# scheme1.net
KiCad netlist of a schematic drawn in EAGLE
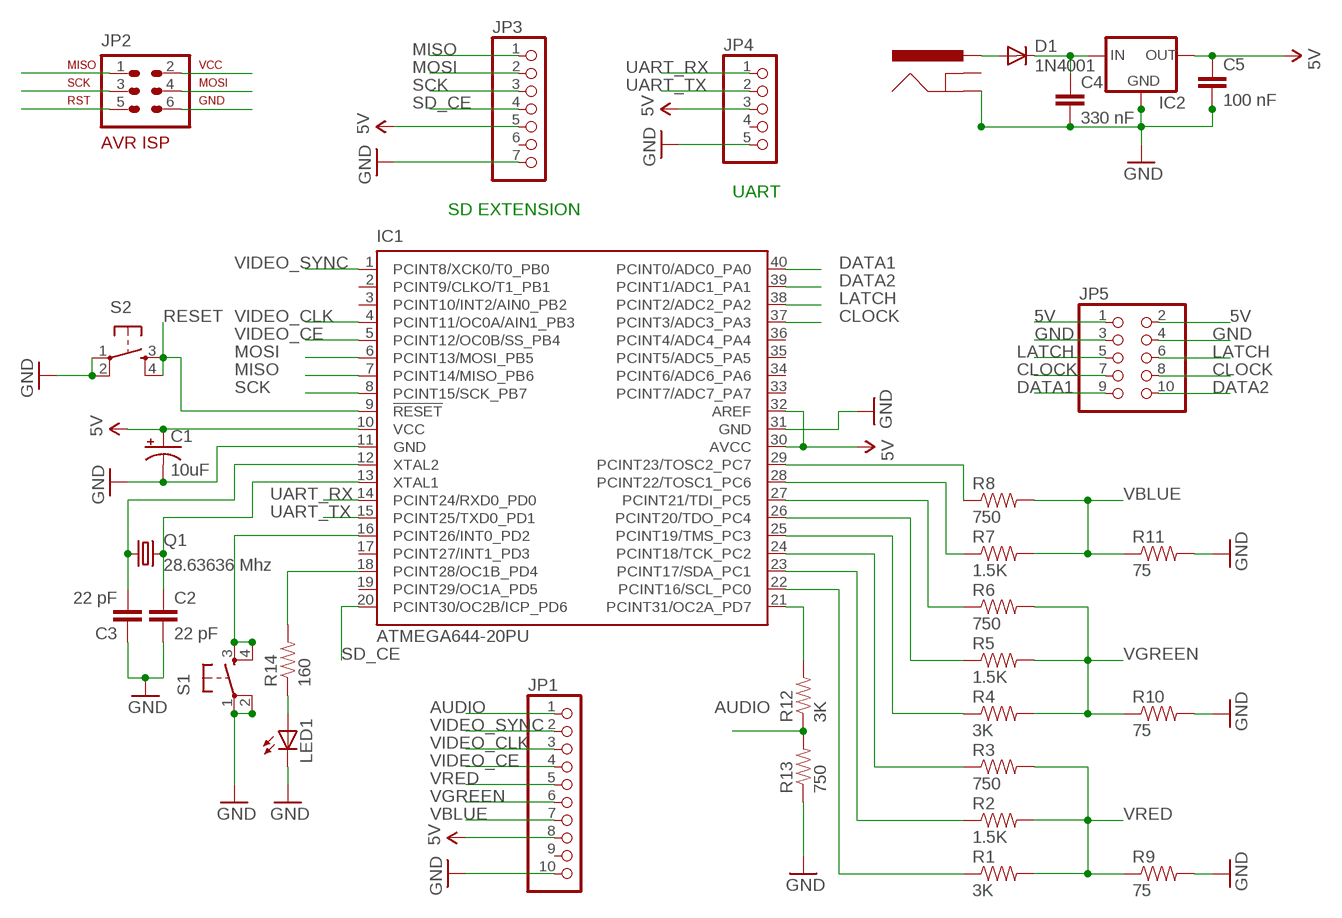
[diagram p0: schematic, sheet 1]

(export (version "E")
  (design (tool "Eeschema 10.0.6"))
  (components
    (comp (ref "C1")
      (value "10uF")
      (footprint "eagle-import:CPOL-RADIAL-10UF-25V")
      (libsource (lib "eagle-import") (part "CAP_POLPTH2"))
    )
    (comp (ref "C2")
      (value "22 pF")
      (footprint "eagle-import:CAP-PTH-SMALL")
      (libsource (lib "eagle-import") (part "CAPPTH"))
    )
    (comp (ref "C3")
      (value "22 pF")
      (footprint "eagle-import:CAP-PTH-SMALL")
      (libsource (lib "eagle-import") (part "CAPPTH"))
    )
    (comp (ref "C4")
      (value "330 nF")
      (footprint "eagle-import:CAP-PTH-SMALL")
      (libsource (lib "eagle-import") (part "CAPPTH"))
    )
    (comp (ref "C5")
      (value "100 nF")
      (footprint "eagle-import:CAP-PTH-SMALL")
      (libsource (lib "eagle-import") (part "CAPPTH"))
    )
    (comp (ref "D1")
      (value "1N4001")
      (footprint "eagle-import:DIODE-1N4001")
      (libsource (lib "eagle-import") (part "DIODEPTH"))
    )
    (comp (ref "IC1")
      (value "ATMEGA644-20PU")
      (footprint "eagle-import:DIL40")
      (libsource (lib "eagle-import") (part "ATMEGA644-PU20"))
    )
    (comp (ref "IC2")
      (value "V_REG_78XXSIDE")
      (footprint "eagle-import:78XXL")
      (libsource (lib "eagle-import") (part "V_REG_78XXSIDE"))
    )
    (comp (ref "J1")
      (value "POWER_JACKSLT")
      (footprint "eagle-import:POWER_JACK_SLOT")
      (libsource (lib "eagle-import") (part "POWER_JACKSLT"))
    )
    (comp (ref "JP1")
      (value "PINHD-1X10")
      (footprint "eagle-import:1X10")
      (libsource (lib "eagle-import") (part "PINHD-1X10"))
    )
    (comp (ref "JP2")
      (value "AVR-ISP-6VERT")
      (footprint "eagle-import:AVR-ISP-6")
      (libsource (lib "eagle-import") (part "AVR-ISP-6VERT"))
    )
    (comp (ref "JP3")
      (value "PINHD-1X7")
      (footprint "eagle-import:1X07")
      (libsource (lib "eagle-import") (part "PINHD-1X7"))
    )
    (comp (ref "JP4")
      (value "PINHD-1X5")
      (footprint "eagle-import:1X05")
      (libsource (lib "eagle-import") (part "PINHD-1X5"))
    )
    (comp (ref "JP5")
      (value "PINHD-2X5")
      (footprint "eagle-import:2X05")
      (libsource (lib "eagle-import") (part "PINHD-2X5"))
    )
    (comp (ref "LED1")
      (value "LED3MM")
      (footprint "eagle-import:LED3MM")
      (libsource (lib "eagle-import") (part "LED3MM"))
    )
    (comp (ref "Q1")
      (value "28.63636 Mhz")
      (footprint "eagle-import:HC49US")
      (libsource (lib "eagle-import") (part "CRYSTALHC49US"))
    )
    (comp (ref "R1")
      (value "3K")
      (footprint "eagle-import:AXIAL-0.3")
      (libsource (lib "eagle-import") (part "RESISTORPTH1"))
    )
    (comp (ref "R2")
      (value "1.5K")
      (footprint "eagle-import:AXIAL-0.3")
      (libsource (lib "eagle-import") (part "RESISTORPTH1"))
    )
    (comp (ref "R3")
      (value "750")
      (footprint "eagle-import:AXIAL-0.3")
      (libsource (lib "eagle-import") (part "RESISTORPTH1"))
    )
    (comp (ref "R4")
      (value "3K")
      (footprint "eagle-import:AXIAL-0.3")
      (libsource (lib "eagle-import") (part "RESISTORPTH1"))
    )
    (comp (ref "R5")
      (value "1.5K")
      (footprint "eagle-import:AXIAL-0.3")
      (libsource (lib "eagle-import") (part "RESISTORPTH1"))
    )
    (comp (ref "R6")
      (value "750")
      (footprint "eagle-import:AXIAL-0.3")
      (libsource (lib "eagle-import") (part "RESISTORPTH1"))
    )
    (comp (ref "R7")
      (value "1.5K")
      (footprint "eagle-import:AXIAL-0.3")
      (libsource (lib "eagle-import") (part "RESISTORPTH1"))
    )
    (comp (ref "R8")
      (value "750")
      (footprint "eagle-import:AXIAL-0.3")
      (libsource (lib "eagle-import") (part "RESISTORPTH1"))
    )
    (comp (ref "R9")
      (value "75")
      (footprint "eagle-import:AXIAL-0.3")
      (libsource (lib "eagle-import") (part "RESISTORPTH1"))
    )
    (comp (ref "R10")
      (value "75")
      (footprint "eagle-import:AXIAL-0.3")
      (libsource (lib "eagle-import") (part "RESISTORPTH1"))
    )
    (comp (ref "R11")
      (value "75")
      (footprint "eagle-import:AXIAL-0.3")
      (libsource (lib "eagle-import") (part "RESISTORPTH1"))
    )
    (comp (ref "R12")
      (value "3K")
      (footprint "eagle-import:AXIAL-0.3")
      (libsource (lib "eagle-import") (part "RESISTORPTH1"))
    )
    (comp (ref "R13")
      (value "750")
      (footprint "eagle-import:AXIAL-0.3")
      (libsource (lib "eagle-import") (part "RESISTORPTH1"))
    )
    (comp (ref "R14")
      (value "160")
      (footprint "eagle-import:AXIAL-0.3")
      (libsource (lib "eagle-import") (part "RESISTORPTH1"))
    )
    (comp (ref "S1")
      (value "TAC_SWITCHPTH")
      (footprint "eagle-import:TACTILE-PTH")
      (libsource (lib "eagle-import") (part "TAC_SWITCHPTH"))
    )
    (comp (ref "S2")
      (value "TAC_SWITCHPTH")
      (footprint "eagle-import:TACTILE-PTH")
      (libsource (lib "eagle-import") (part "TAC_SWITCHPTH"))
    )
  )
  (nets
    (net (code "1") (name "/AUDIO") (class "Default")
      (node (ref "JP1") (pin "1") (pinfunction "1_1") (pintype "passive"))
      (node (ref "R12") (pin "P$1") (pinfunction "1_P$1") (pintype "passive"))
      (node (ref "R13") (pin "P$2") (pinfunction "2_P$2") (pintype "passive"))
    )
    (net (code "2") (name "/CLOCK") (class "Default")
      (node (ref "IC1") (pin "37") (pinfunction "PCINT3/ADC3_PA3_37") (pintype "bidirectional"))
      (node (ref "JP5") (pin "7") (pinfunction "7_7") (pintype "passive"))
      (node (ref "JP5") (pin "8") (pinfunction "8_8") (pintype "passive"))
    )
    (net (code "3") (name "/DATA1") (class "Default")
      (node (ref "IC1") (pin "40") (pinfunction "PCINT0/ADC0_PA0_40") (pintype "bidirectional"))
      (node (ref "JP5") (pin "9") (pinfunction "9_9") (pintype "passive"))
    )
    (net (code "4") (name "/DATA2") (class "Default")
      (node (ref "IC1") (pin "39") (pinfunction "PCINT1/ADC1_PA1_39") (pintype "bidirectional"))
      (node (ref "JP5") (pin "10") (pinfunction "10_10") (pintype "passive"))
    )
    (net (code "5") (name "/LATCH") (class "Default")
      (node (ref "IC1") (pin "38") (pinfunction "PCINT2/ADC2_PA2_38") (pintype "bidirectional"))
      (node (ref "JP5") (pin "5") (pinfunction "5_5") (pintype "passive"))
      (node (ref "JP5") (pin "6") (pinfunction "6_6") (pintype "passive"))
    )
    (net (code "6") (name "/MISO") (class "Default")
      (node (ref "IC1") (pin "7") (pinfunction "PCINT14/MISO_PB6_7") (pintype "bidirectional"))
      (node (ref "JP2") (pin "1") (pinfunction "1_1") (pintype "passive"))
      (node (ref "JP3") (pin "1") (pinfunction "1_1") (pintype "passive"))
    )
    (net (code "7") (name "/MOSI") (class "Default")
      (node (ref "IC1") (pin "6") (pinfunction "PCINT13/MOSI_PB5_6") (pintype "bidirectional"))
      (node (ref "JP2") (pin "4") (pinfunction "4_4") (pintype "passive"))
      (node (ref "JP3") (pin "2") (pinfunction "2_2") (pintype "passive"))
    )
    (net (code "8") (name "/RESET") (class "Default")
      (node (ref "IC1") (pin "9") (pinfunction "~{RESET}_9") (pintype "input"))
      (node (ref "JP2") (pin "5") (pinfunction "5_5") (pintype "passive"))
      (node (ref "S2") (pin "3") (pinfunction "3_3") (pintype "passive"))
      (node (ref "S2") (pin "4") (pinfunction "4_4") (pintype "passive"))
    )
    (net (code "9") (name "/SCK") (class "Default")
      (node (ref "IC1") (pin "8") (pinfunction "PCINT15/SCK_PB7_8") (pintype "bidirectional"))
      (node (ref "JP2") (pin "3") (pinfunction "3_3") (pintype "passive"))
      (node (ref "JP3") (pin "3") (pinfunction "3_3") (pintype "passive"))
    )
    (net (code "10") (name "/SD_CE") (class "Default")
      (node (ref "IC1") (pin "20") (pinfunction "PCINT30/OC2B/ICP_PD6_20") (pintype "bidirectional"))
      (node (ref "JP3") (pin "4") (pinfunction "4_4") (pintype "passive"))
    )
    (net (code "11") (name "/UART_RX") (class "Default")
      (node (ref "IC1") (pin "14") (pinfunction "PCINT24/RXD0_PD0_14") (pintype "bidirectional"))
      (node (ref "JP4") (pin "1") (pinfunction "1_1") (pintype "passive"))
    )
    (net (code "12") (name "/UART_TX") (class "Default")
      (node (ref "IC1") (pin "15") (pinfunction "PCINT25/TXD0_PD1_15") (pintype "bidirectional"))
      (node (ref "JP4") (pin "2") (pinfunction "2_2") (pintype "passive"))
    )
    (net (code "13") (name "/VBLUE") (class "Default")
      (node (ref "JP1") (pin "7") (pinfunction "7_7") (pintype "passive"))
      (node (ref "R11") (pin "P$1") (pinfunction "1_P$1") (pintype "passive"))
      (node (ref "R7") (pin "P$2") (pinfunction "2_P$2") (pintype "passive"))
      (node (ref "R8") (pin "P$2") (pinfunction "2_P$2") (pintype "passive"))
    )
    (net (code "14") (name "/VGREEN") (class "Default")
      (node (ref "JP1") (pin "6") (pinfunction "6_6") (pintype "passive"))
      (node (ref "R10") (pin "P$1") (pinfunction "1_P$1") (pintype "passive"))
      (node (ref "R4") (pin "P$2") (pinfunction "2_P$2") (pintype "passive"))
      (node (ref "R5") (pin "P$2") (pinfunction "2_P$2") (pintype "passive"))
      (node (ref "R6") (pin "P$2") (pinfunction "2_P$2") (pintype "passive"))
    )
    (net (code "15") (name "/VIDEO_CE") (class "Default")
      (node (ref "IC1") (pin "5") (pinfunction "PCINT12/OC0B/SS_PB4_5") (pintype "bidirectional"))
      (node (ref "JP1") (pin "4") (pinfunction "4_4") (pintype "passive"))
    )
    (net (code "16") (name "/VIDEO_CLK") (class "Default")
      (node (ref "IC1") (pin "4") (pinfunction "PCINT11/OC0A/AIN1_PB3_4") (pintype "bidirectional"))
      (node (ref "JP1") (pin "3") (pinfunction "3_3") (pintype "passive"))
    )
    (net (code "17") (name "/VIDEO_SYNC") (class "Default")
      (node (ref "IC1") (pin "1") (pinfunction "PCINT8/XCK0/T0_PB0_1") (pintype "bidirectional"))
      (node (ref "JP1") (pin "2") (pinfunction "2_2") (pintype "passive"))
    )
    (net (code "18") (name "/VRED") (class "Default")
      (node (ref "JP1") (pin "5") (pinfunction "5_5") (pintype "passive"))
      (node (ref "R1") (pin "P$2") (pinfunction "2_P$2") (pintype "passive"))
      (node (ref "R2") (pin "P$2") (pinfunction "2_P$2") (pintype "passive"))
      (node (ref "R3") (pin "P$2") (pinfunction "2_P$2") (pintype "passive"))
      (node (ref "R9") (pin "P$1") (pinfunction "1_P$1") (pintype "passive"))
    )
    (net (code "19") (name "5V") (class "Default")
      (node (ref "C1") (pin "1") (pinfunction "+_1") (pintype "passive"))
      (node (ref "C5") (pin "1") (pinfunction "1_1") (pintype "passive"))
      (node (ref "IC1") (pin "10") (pinfunction "VCC_10") (pintype "power_in"))
      (node (ref "IC1") (pin "30") (pinfunction "AVCC_30") (pintype "power_in"))
      (node (ref "IC1") (pin "32") (pinfunction "AREF_32") (pintype "passive"))
      (node (ref "IC2") (pin "OUT") (pinfunction "OUT_OUT") (pintype "output"))
      (node (ref "JP1") (pin "8") (pinfunction "8_8") (pintype "passive"))
      (node (ref "JP2") (pin "2") (pinfunction "2_2") (pintype "passive"))
      (node (ref "JP3") (pin "5") (pinfunction "5_5") (pintype "passive"))
      (node (ref "JP4") (pin "3") (pinfunction "3_3") (pintype "passive"))
      (node (ref "JP5") (pin "1") (pinfunction "1_1") (pintype "passive"))
      (node (ref "JP5") (pin "2") (pinfunction "2_2") (pintype "passive"))
    )
    (net (code "20") (name "GND") (class "Default")
      (node (ref "C1") (pin "2") (pinfunction "-_2") (pintype "passive"))
      (node (ref "C2") (pin "2") (pinfunction "2_2") (pintype "passive"))
      (node (ref "C3") (pin "1") (pinfunction "1_1") (pintype "passive"))
      (node (ref "C4") (pin "2") (pinfunction "2_2") (pintype "passive"))
      (node (ref "C5") (pin "2") (pinfunction "2_2") (pintype "passive"))
      (node (ref "IC1") (pin "11") (pinfunction "GND_11") (pintype "power_in"))
      (node (ref "IC1") (pin "31") (pinfunction "GND_31") (pintype "power_in"))
      (node (ref "IC2") (pin "GND") (pinfunction "GND_GND") (pintype "input"))
      (node (ref "J1") (pin "GND@2") (pinfunction "GND_GND@2") (pintype "bidirectional"))
      (node (ref "JP1") (pin "10") (pinfunction "10_10") (pintype "passive"))
      (node (ref "JP2") (pin "6") (pinfunction "6_6") (pintype "passive"))
      (node (ref "JP3") (pin "7") (pinfunction "7_7") (pintype "passive"))
      (node (ref "JP4") (pin "5") (pinfunction "5_5") (pintype "passive"))
      (node (ref "JP5") (pin "3") (pinfunction "3_3") (pintype "passive"))
      (node (ref "JP5") (pin "4") (pinfunction "4_4") (pintype "passive"))
      (node (ref "LED1") (pin "K") (pinfunction "C_K") (pintype "passive"))
      (node (ref "R10") (pin "P$2") (pinfunction "2_P$2") (pintype "passive"))
      (node (ref "R11") (pin "P$2") (pinfunction "2_P$2") (pintype "passive"))
      (node (ref "R13") (pin "P$1") (pinfunction "1_P$1") (pintype "passive"))
      (node (ref "R9") (pin "P$2") (pinfunction "2_P$2") (pintype "passive"))
      (node (ref "S1") (pin "1") (pinfunction "1_1") (pintype "passive"))
      (node (ref "S1") (pin "2") (pinfunction "2_2") (pintype "passive"))
      (node (ref "S2") (pin "1") (pinfunction "1_1") (pintype "passive"))
      (node (ref "S2") (pin "2") (pinfunction "2_2") (pintype "passive"))
    )
    (net (code "21") (name "Net-(C4-Pad1)") (class "Default")
      (node (ref "C4") (pin "1") (pinfunction "1_1") (pintype "passive"))
      (node (ref "D1") (pin "C") (pinfunction "C_C") (pintype "passive"))
      (node (ref "IC2") (pin "IN") (pinfunction "IN_IN") (pintype "input"))
    )
    (net (code "22") (name "Net-(D1-PadA)") (class "Default")
      (node (ref "D1") (pin "A") (pinfunction "A_A") (pintype "passive"))
      (node (ref "J1") (pin "PWR") (pinfunction "PWR_PWR") (pintype "bidirectional"))
    )
    (net (code "23") (name "Net-(IC1-PCINT16{slash}SCL_PC0)") (class "Default")
      (node (ref "IC1") (pin "22") (pinfunction "PCINT16/SCL_PC0_22") (pintype "bidirectional"))
      (node (ref "R1") (pin "P$1") (pinfunction "1_P$1") (pintype "passive"))
    )
    (net (code "24") (name "Net-(IC1-PCINT17{slash}SDA_PC1)") (class "Default")
      (node (ref "IC1") (pin "23") (pinfunction "PCINT17/SDA_PC1_23") (pintype "bidirectional"))
      (node (ref "R2") (pin "P$1") (pinfunction "1_P$1") (pintype "passive"))
    )
    (net (code "25") (name "Net-(IC1-PCINT18{slash}TCK_PC2)") (class "Default")
      (node (ref "IC1") (pin "24") (pinfunction "PCINT18/TCK_PC2_24") (pintype "bidirectional"))
      (node (ref "R3") (pin "P$1") (pinfunction "1_P$1") (pintype "passive"))
    )
    (net (code "26") (name "Net-(IC1-PCINT19{slash}TMS_PC3)") (class "Default")
      (node (ref "IC1") (pin "25") (pinfunction "PCINT19/TMS_PC3_25") (pintype "bidirectional"))
      (node (ref "R4") (pin "P$1") (pinfunction "1_P$1") (pintype "passive"))
    )
    (net (code "27") (name "Net-(IC1-PCINT20{slash}TDO_PC4)") (class "Default")
      (node (ref "IC1") (pin "26") (pinfunction "PCINT20/TDO_PC4_26") (pintype "bidirectional"))
      (node (ref "R5") (pin "P$1") (pinfunction "1_P$1") (pintype "passive"))
    )
    (net (code "28") (name "Net-(IC1-PCINT21{slash}TDI_PC5)") (class "Default")
      (node (ref "IC1") (pin "27") (pinfunction "PCINT21/TDI_PC5_27") (pintype "bidirectional"))
      (node (ref "R6") (pin "P$1") (pinfunction "1_P$1") (pintype "passive"))
    )
    (net (code "29") (name "Net-(IC1-PCINT22{slash}TOSC1_PC6)") (class "Default")
      (node (ref "IC1") (pin "28") (pinfunction "PCINT22/TOSC1_PC6_28") (pintype "bidirectional"))
      (node (ref "R7") (pin "P$1") (pinfunction "1_P$1") (pintype "passive"))
    )
    (net (code "30") (name "Net-(IC1-PCINT23{slash}TOSC2_PC7)") (class "Default")
      (node (ref "IC1") (pin "29") (pinfunction "PCINT23/TOSC2_PC7_29") (pintype "bidirectional"))
      (node (ref "R8") (pin "P$1") (pinfunction "1_P$1") (pintype "passive"))
    )
    (net (code "31") (name "Net-(IC1-PCINT26{slash}INT0_PD2)") (class "Default")
      (node (ref "IC1") (pin "16") (pinfunction "PCINT26/INT0_PD2_16") (pintype "bidirectional"))
      (node (ref "S1") (pin "3") (pinfunction "3_3") (pintype "passive"))
      (node (ref "S1") (pin "4") (pinfunction "4_4") (pintype "passive"))
    )
    (net (code "32") (name "Net-(IC1-PCINT28{slash}OC1B_PD4)") (class "Default")
      (node (ref "IC1") (pin "18") (pinfunction "PCINT28/OC1B_PD4_18") (pintype "bidirectional"))
      (node (ref "R14") (pin "P$2") (pinfunction "2_P$2") (pintype "passive"))
    )
    (net (code "33") (name "Net-(IC1-PCINT31{slash}OC2A_PD7)") (class "Default")
      (node (ref "IC1") (pin "21") (pinfunction "PCINT31/OC2A_PD7_21") (pintype "bidirectional"))
      (node (ref "R12") (pin "P$2") (pinfunction "2_P$2") (pintype "passive"))
    )
    (net (code "34") (name "Net-(IC1-XTAL1)") (class "Default")
      (node (ref "C2") (pin "1") (pinfunction "1_1") (pintype "passive"))
      (node (ref "IC1") (pin "13") (pinfunction "XTAL1_13") (pintype "input"))
      (node (ref "Q1") (pin "2") (pinfunction "2_2") (pintype "passive"))
    )
    (net (code "35") (name "Net-(IC1-XTAL2)") (class "Default")
      (node (ref "C3") (pin "2") (pinfunction "2_2") (pintype "passive"))
      (node (ref "IC1") (pin "12") (pinfunction "XTAL2_12") (pintype "output"))
      (node (ref "Q1") (pin "1") (pinfunction "1_1") (pintype "passive"))
    )
    (net (code "36") (name "Net-(R14-1)") (class "Default")
      (node (ref "LED1") (pin "A") (pinfunction "A_A") (pintype "passive"))
      (node (ref "R14") (pin "P$1") (pinfunction "1_P$1") (pintype "passive"))
    )
    (net (code "37") (name "unconnected-(IC1-PCINT4{slash}ADC4_PA4-Pad36)") (class "Default")
      (node (ref "IC1") (pin "36") (pinfunction "PCINT4/ADC4_PA4_36") (pintype "bidirectional"))
    )
    (net (code "38") (name "unconnected-(IC1-PCINT5{slash}ADC5_PA5-Pad35)") (class "Default")
      (node (ref "IC1") (pin "35") (pinfunction "PCINT5/ADC5_PA5_35") (pintype "bidirectional"))
    )
    (net (code "39") (name "unconnected-(IC1-PCINT6{slash}ADC6_PA6-Pad34)") (class "Default")
      (node (ref "IC1") (pin "34") (pinfunction "PCINT6/ADC6_PA6_34") (pintype "bidirectional"))
    )
    (net (code "40") (name "unconnected-(IC1-PCINT7{slash}ADC7_PA7-Pad33)") (class "Default")
      (node (ref "IC1") (pin "33") (pinfunction "PCINT7/ADC7_PA7_33") (pintype "bidirectional"))
    )
    (net (code "41") (name "unconnected-(IC1-PCINT9{slash}CLKO{slash}T1_PB1-Pad2)") (class "Default")
      (node (ref "IC1") (pin "2") (pinfunction "PCINT9/CLKO/T1_PB1_2") (pintype "bidirectional"))
    )
    (net (code "42") (name "unconnected-(IC1-PCINT10{slash}INT2{slash}AIN0_PB2-Pad3)") (class "Default")
      (node (ref "IC1") (pin "3") (pinfunction "PCINT10/INT2/AIN0_PB2_3") (pintype "bidirectional"))
    )
    (net (code "43") (name "unconnected-(IC1-PCINT27{slash}INT1_PD3-Pad17)") (class "Default")
      (node (ref "IC1") (pin "17") (pinfunction "PCINT27/INT1_PD3_17") (pintype "bidirectional"))
    )
    (net (code "44") (name "unconnected-(IC1-PCINT29{slash}OC1A_PD5-Pad19)") (class "Default")
      (node (ref "IC1") (pin "19") (pinfunction "PCINT29/OC1A_PD5_19") (pintype "bidirectional"))
    )
    (net (code "45") (name "unconnected-(J1-GNDBREAK-PadGND@1)") (class "Default")
      (node (ref "J1") (pin "GND@1") (pinfunction "GNDBREAK_GND@1") (pintype "bidirectional"))
    )
    (net (code "46") (name "unconnected-(JP1-Pad9)") (class "Default")
      (node (ref "JP1") (pin "9") (pinfunction "9_9") (pintype "passive"))
    )
    (net (code "47") (name "unconnected-(JP3-Pad6)") (class "Default")
      (node (ref "JP3") (pin "6") (pinfunction "6_6") (pintype "passive"))
    )
    (net (code "48") (name "unconnected-(JP4-Pad4)") (class "Default")
      (node (ref "JP4") (pin "4") (pinfunction "4_4") (pintype "passive"))
    )
  )
)
